# 6_Channels_TX_V1_Schematic.net
KiCad netlist of a schematic drawn in Altium Designer
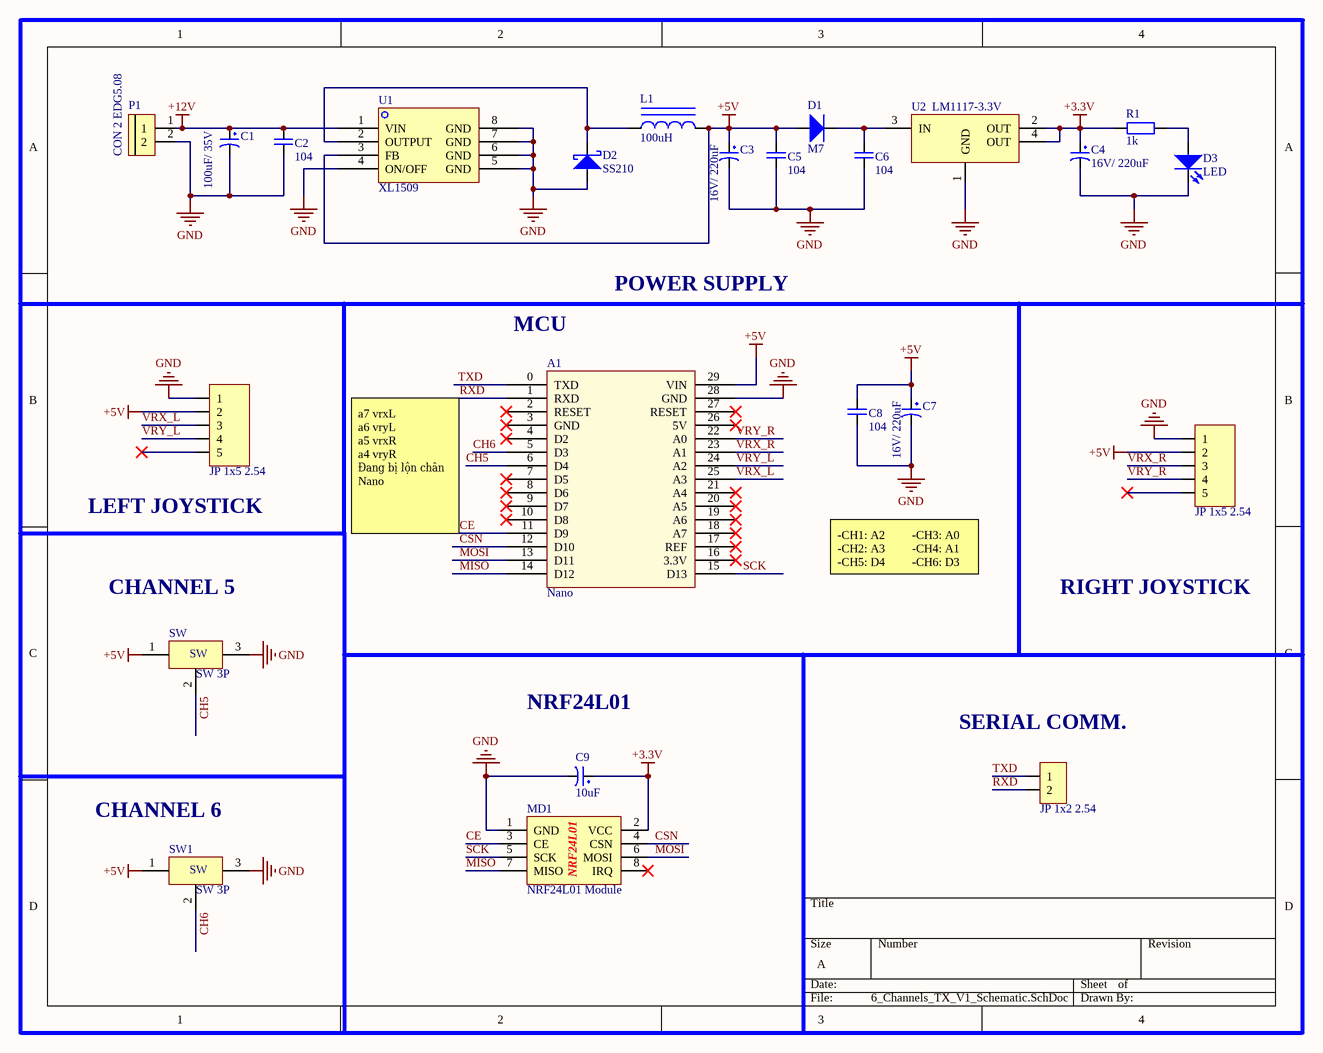
[diagram p0: 6_Channels_TX_V1_Schematic.SchDoc]

(export (version "E")
  (design (tool "Eeschema 10.0.6"))
  (components
    (comp (ref "A1")
      (value "Nano")
      (footprint "Arduino nano")
      (libsource (lib "Altium_Lib_by_KhueNguyenCreator") (part "Arduino Nano"))
    )
    (comp (ref "C1")
      (value "100uF/ 35V")
      (footprint "CAP SMD ALUMINUM D8")
      (libsource (lib "Electronic4u") (part "Cap_Polar"))
    )
    (comp (ref "C2")
      (value "104")
      (footprint "SM-0805")
      (libsource (lib "Electronic4u") (part "Cap_Non-Polar"))
    )
    (comp (ref "C3")
      (value "16V/ 220uF")
      (footprint "CAP SMD ALUMINUM D8")
      (libsource (lib "Electronic4u") (part "Cap_Polar"))
    )
    (comp (ref "C4")
      (value "16V/ 220uF")
      (footprint "CAP SMD ALUMINUM D8")
      (libsource (lib "Electronic4u") (part "Cap_Polar"))
    )
    (comp (ref "C5")
      (value "104")
      (footprint "SM-0805")
      (libsource (lib "Electronic4u") (part "Cap_Non-Polar"))
    )
    (comp (ref "C6")
      (value "104")
      (footprint "SM-0805")
      (libsource (lib "Electronic4u") (part "Cap_Non-Polar"))
    )
    (comp (ref "C7")
      (value "16V/ 220uF")
      (footprint "CAP SMD ALUMINUM D8")
      (libsource (lib "Electronic4u") (part "Cap_Polar"))
    )
    (comp (ref "C8")
      (value "104")
      (footprint "SM-0805")
      (libsource (lib "Electronic4u") (part "Cap_Non-Polar"))
    )
    (comp (ref "C9")
      (value "10uF")
      (footprint "tu hoa 8mm")
      (description "Cắm")
      (libsource (lib "Altium_Lib_by_KhueNguyenCreator") (part "Tu Hoa 100uF 35V 8x11"))
    )
    (comp (ref "D1")
      (value "M7")
      (footprint "DO-214AC")
      (description "Diode Standard")
      (fields (field (name "PART NUMBER") "LED 3 ly Single Colour"))
      (libsource (lib "Electronic4u") (part "Diode Standard"))
    )
    (comp (ref "D2")
      (value "SS210")
      (footprint "DO-214AC")
      (description "Diode Schottky")
      (fields (field (name "PART NUMBER") "LED 3 ly Single Colour"))
      (libsource (lib "Electronic4u") (part "Diode Schottky"))
    )
    (comp (ref "D3")
      (value "LED")
      (footprint "LED-3MM GRE")
      (description "LED Single")
      (libsource (lib "Electronic4u") (part "LED"))
    )
    (comp (ref "JP1")
      (value "JP 1x5 2.54")
      (footprint "JP 1x5 CC")
      (description "Cắm")
      (libsource (lib "Altium_Lib_by_KhueNguyenCreator") (part "JP 1x5 2.54 Cai Cong"))
    )
    (comp (ref "JP2")
      (value "JP 1x5 2.54")
      (footprint "JP 1x5 CC")
      (description "Cắm")
      (libsource (lib "Altium_Lib_by_KhueNguyenCreator") (part "JP 1x5 2.54 Cai Cong"))
    )
    (comp (ref "JP3")
      (value "JP 1x2 2.54")
      (footprint "JP 1x2 DT")
      (description "Cắm")
      (libsource (lib "Altium_Lib_by_KhueNguyenCreator") (part "JP 1x2 2.54 Duc Thang"))
    )
    (comp (ref "L1")
      (value "100uH")
      (footprint "INDUCTOR SMD 7342 7.3X7.3X4.2mm")
      (description "Magnetic-Core Inductor")
      (libsource (lib "Electronic4u") (part "Inductor Iron"))
    )
    (comp (ref "MD1")
      (value "NRF24L01 Module")
      (footprint "NRF24L01")
      (libsource (lib "Altium_Lib_by_KhueNguyenCreator") (part "NRF24L01 Module"))
    )
    (comp (ref "P1")
      (value "CON 2 EDG5.08")
      (footprint "CON 2 2EDG5.08")
      (description "Cắm")
      (libsource (lib "Altium_Lib_by_KhueNguyenCreator") (part "CON 2 EDG5.08"))
    )
    (comp (ref "R1")
      (value "1k")
      (footprint "RESISTOR SMD 0805")
      (libsource (lib "Electronic4u") (part "Resistor"))
    )
    (comp (ref "SW") (value "SW 3P") (footprint "MTS-102") (libsource (lib "FMS_PcbLib1") (part "SW 3P")))
    (comp (ref "SW1") (value "SW 3P") (footprint "MTS-102") (libsource (lib "FMS_PcbLib1") (part "SW 3P")))
    (comp (ref "U1")
      (value "XL1509")
      (footprint "SOP8")
      (description "IC power sop8")
      (libsource (lib "FMS_PcbLib1") (part "XL1509"))
    )
    (comp (ref "U2")
      (value "LM1117-3.3V")
      (footprint "SOT223-4N")
      (description "800mA Low-Dropout Linear Regulator")
      (fields (field (name "CREATOR") "Nguyen Ba Bien"))
      (libsource (lib "Electronic4u") (part "LM1117"))
    )
  )
  (nets
    (net (code "1") (name "+3.3V") (class "Default")
      (node (ref "C4") (pin "1") (pinfunction "1_1") (pintype "passive"))
      (node (ref "C9") (pin "1") (pinfunction "1_1") (pintype "passive"))
      (node (ref "MD1") (pin "2") (pinfunction "VCC_2") (pintype "passive"))
      (node (ref "R1") (pin "1") (pinfunction "1_1") (pintype "passive"))
      (node (ref "U2") (pin "2") (pinfunction "OUT_2") (pintype "passive"))
      (node (ref "U2") (pin "4") (pinfunction "OUT_4") (pintype "passive"))
    )
    (net (code "2") (name "+5V") (class "Default")
      (node (ref "A1") (pin "29") (pinfunction "VIN_29") (pintype "passive"))
      (node (ref "C3") (pin "1") (pinfunction "1_1") (pintype "passive"))
      (node (ref "C5") (pin "2") (pinfunction "2_2") (pintype "passive"))
      (node (ref "C7") (pin "1") (pinfunction "1_1") (pintype "passive"))
      (node (ref "C8") (pin "2") (pinfunction "2_2") (pintype "passive"))
      (node (ref "D1") (pin "1") (pinfunction "1_1") (pintype "passive"))
      (node (ref "JP1") (pin "2") (pinfunction "2_2") (pintype "passive"))
      (node (ref "JP2") (pin "2") (pinfunction "2_2") (pintype "passive"))
      (node (ref "L1") (pin "2") (pinfunction "2_2") (pintype "passive"))
      (node (ref "SW") (pin "1") (pinfunction "1_1") (pintype "passive"))
      (node (ref "SW1") (pin "1") (pinfunction "1_1") (pintype "passive"))
      (node (ref "U1") (pin "3") (pinfunction "FB_3") (pintype "passive"))
    )
    (net (code "3") (name "+12V") (class "Default")
      (node (ref "C1") (pin "1") (pinfunction "1_1") (pintype "passive"))
      (node (ref "C2") (pin "2") (pinfunction "2_2") (pintype "passive"))
      (node (ref "P1") (pin "1") (pinfunction "1_1") (pintype "passive"))
      (node (ref "U1") (pin "1") (pinfunction "VIN_1") (pintype "passive"))
    )
    (net (code "4") (name "/CE") (class "Default")
      (node (ref "A1") (pin "11") (pinfunction "D9_11") (pintype "passive"))
      (node (ref "MD1") (pin "3") (pinfunction "CE_3") (pintype "passive"))
    )
    (net (code "5") (name "/CH5") (class "Default")
      (node (ref "A1") (pin "6") (pinfunction "D4_6") (pintype "passive"))
      (node (ref "SW") (pin "2") (pinfunction "2_2") (pintype "passive"))
    )
    (net (code "6") (name "/CH6") (class "Default")
      (node (ref "A1") (pin "5") (pinfunction "D3_5") (pintype "passive"))
      (node (ref "SW1") (pin "2") (pinfunction "2_2") (pintype "passive"))
    )
    (net (code "7") (name "/CSN") (class "Default")
      (node (ref "A1") (pin "12") (pinfunction "D10_12") (pintype "passive"))
      (node (ref "MD1") (pin "4") (pinfunction "CSN_4") (pintype "passive"))
    )
    (net (code "8") (name "/MISO") (class "Default")
      (node (ref "A1") (pin "14") (pinfunction "D12_14") (pintype "passive"))
      (node (ref "MD1") (pin "7") (pinfunction "MISO_7") (pintype "passive"))
    )
    (net (code "9") (name "/MOSI") (class "Default")
      (node (ref "A1") (pin "13") (pinfunction "D11_13") (pintype "passive"))
      (node (ref "MD1") (pin "6") (pinfunction "MOSI_6") (pintype "passive"))
    )
    (net (code "10") (name "/RXD") (class "Default")
      (node (ref "A1") (pin "1") (pinfunction "RXD_1") (pintype "passive"))
      (node (ref "JP3") (pin "2") (pinfunction "2_2") (pintype "passive"))
    )
    (net (code "11") (name "/SCK") (class "Default")
      (node (ref "A1") (pin "15") (pinfunction "D13_15") (pintype "passive"))
      (node (ref "MD1") (pin "5") (pinfunction "SCK_5") (pintype "passive"))
    )
    (net (code "12") (name "/TXD") (class "Default")
      (node (ref "A1") (pin "0") (pinfunction "TXD_0") (pintype "passive"))
      (node (ref "JP3") (pin "1") (pinfunction "1_1") (pintype "passive"))
    )
    (net (code "13") (name "/VRX_L") (class "Default")
      (node (ref "A1") (pin "25") (pinfunction "A3_25") (pintype "passive"))
      (node (ref "JP1") (pin "3") (pinfunction "3_3") (pintype "passive"))
    )
    (net (code "14") (name "/VRX_R") (class "Default")
      (node (ref "A1") (pin "23") (pinfunction "A1_23") (pintype "passive"))
      (node (ref "JP2") (pin "3") (pinfunction "3_3") (pintype "passive"))
    )
    (net (code "15") (name "/VRY_L") (class "Default")
      (node (ref "A1") (pin "24") (pinfunction "A2_24") (pintype "passive"))
      (node (ref "JP1") (pin "4") (pinfunction "4_4") (pintype "passive"))
    )
    (net (code "16") (name "/VRY_R") (class "Default")
      (node (ref "A1") (pin "22") (pinfunction "A0_22") (pintype "passive"))
      (node (ref "JP2") (pin "4") (pinfunction "4_4") (pintype "passive"))
    )
    (net (code "17") (name "GND") (class "Default")
      (node (ref "A1") (pin "28") (pinfunction "GND_28") (pintype "passive"))
      (node (ref "C1") (pin "2") (pinfunction "2_2") (pintype "passive"))
      (node (ref "C2") (pin "1") (pinfunction "1_1") (pintype "passive"))
      (node (ref "C3") (pin "2") (pinfunction "2_2") (pintype "passive"))
      (node (ref "C4") (pin "2") (pinfunction "2_2") (pintype "passive"))
      (node (ref "C5") (pin "1") (pinfunction "1_1") (pintype "passive"))
      (node (ref "C6") (pin "1") (pinfunction "1_1") (pintype "passive"))
      (node (ref "C7") (pin "2") (pinfunction "2_2") (pintype "passive"))
      (node (ref "C8") (pin "1") (pinfunction "1_1") (pintype "passive"))
      (node (ref "C9") (pin "2") (pinfunction "2_2") (pintype "passive"))
      (node (ref "D2") (pin "1") (pinfunction "1_1") (pintype "passive"))
      (node (ref "D3") (pin "2") (pinfunction "2_2") (pintype "passive"))
      (node (ref "JP1") (pin "1") (pinfunction "1_1") (pintype "passive"))
      (node (ref "JP2") (pin "1") (pinfunction "1_1") (pintype "passive"))
      (node (ref "MD1") (pin "1") (pinfunction "GND_1") (pintype "passive"))
      (node (ref "P1") (pin "2") (pinfunction "2_2") (pintype "passive"))
      (node (ref "SW") (pin "3") (pinfunction "3_3") (pintype "passive"))
      (node (ref "SW1") (pin "3") (pinfunction "3_3") (pintype "passive"))
      (node (ref "U1") (pin "4") (pinfunction "ON/OFF_4") (pintype "passive"))
      (node (ref "U1") (pin "5") (pinfunction "GND_5") (pintype "passive"))
      (node (ref "U1") (pin "6") (pinfunction "GND_6") (pintype "passive"))
      (node (ref "U1") (pin "7") (pinfunction "GND_7") (pintype "passive"))
      (node (ref "U1") (pin "8") (pinfunction "GND_8") (pintype "passive"))
      (node (ref "U2") (pin "1") (pinfunction "GND_1") (pintype "passive"))
    )
    (net (code "18") (name "Net-(D3-Pad1)") (class "Default")
      (node (ref "D3") (pin "1") (pinfunction "1_1") (pintype "passive"))
      (node (ref "R1") (pin "2") (pinfunction "2_2") (pintype "passive"))
    )
    (net (code "19") (name "Net-(U1-OUTPUT)") (class "Default")
      (node (ref "D2") (pin "2") (pinfunction "2_2") (pintype "passive"))
      (node (ref "L1") (pin "1") (pinfunction "1_1") (pintype "passive"))
      (node (ref "U1") (pin "2") (pinfunction "OUTPUT_2") (pintype "passive"))
    )
    (net (code "20") (name "Net-(U2-IN)") (class "Default")
      (node (ref "C6") (pin "2") (pinfunction "2_2") (pintype "passive"))
      (node (ref "D1") (pin "2") (pinfunction "2_2") (pintype "passive"))
      (node (ref "U2") (pin "3") (pinfunction "IN_3") (pintype "passive"))
    )
    (net (code "21") (name "unconnected-(A1-3.3V-Pad16)") (class "Default")
      (node (ref "A1") (pin "16") (pinfunction "3.3V_16") (pintype "passive+no_connect"))
    )
    (net (code "22") (name "unconnected-(A1-5V-Pad26)") (class "Default")
      (node (ref "A1") (pin "26") (pinfunction "5V_26") (pintype "passive+no_connect"))
    )
    (net (code "23") (name "unconnected-(A1-A4-Pad21)") (class "Default")
      (node (ref "A1") (pin "21") (pinfunction "A4_21") (pintype "passive+no_connect"))
    )
    (net (code "24") (name "unconnected-(A1-A5-Pad20)") (class "Default")
      (node (ref "A1") (pin "20") (pinfunction "A5_20") (pintype "passive+no_connect"))
    )
    (net (code "25") (name "unconnected-(A1-A6-Pad19)") (class "Default")
      (node (ref "A1") (pin "19") (pinfunction "A6_19") (pintype "passive+no_connect"))
    )
    (net (code "26") (name "unconnected-(A1-A7-Pad18)") (class "Default")
      (node (ref "A1") (pin "18") (pinfunction "A7_18") (pintype "passive+no_connect"))
    )
    (net (code "27") (name "unconnected-(A1-D2-Pad4)") (class "Default")
      (node (ref "A1") (pin "4") (pinfunction "D2_4") (pintype "passive+no_connect"))
    )
    (net (code "28") (name "unconnected-(A1-D5-Pad7)") (class "Default")
      (node (ref "A1") (pin "7") (pinfunction "D5_7") (pintype "passive+no_connect"))
    )
    (net (code "29") (name "unconnected-(A1-D6-Pad8)") (class "Default")
      (node (ref "A1") (pin "8") (pinfunction "D6_8") (pintype "passive+no_connect"))
    )
    (net (code "30") (name "unconnected-(A1-D7-Pad9)") (class "Default")
      (node (ref "A1") (pin "9") (pinfunction "D7_9") (pintype "passive+no_connect"))
    )
    (net (code "31") (name "unconnected-(A1-D8-Pad10)") (class "Default")
      (node (ref "A1") (pin "10") (pinfunction "D8_10") (pintype "passive+no_connect"))
    )
    (net (code "32") (name "unconnected-(A1-GND-Pad3)") (class "Default")
      (node (ref "A1") (pin "3") (pinfunction "GND_3") (pintype "passive+no_connect"))
    )
    (net (code "33") (name "unconnected-(A1-REF-Pad17)") (class "Default")
      (node (ref "A1") (pin "17") (pinfunction "REF_17") (pintype "passive+no_connect"))
    )
    (net (code "34") (name "unconnected-(A1-RESET-Pad2)") (class "Default")
      (node (ref "A1") (pin "2") (pinfunction "RESET_2") (pintype "passive+no_connect"))
    )
    (net (code "35") (name "unconnected-(A1-RESET-Pad27)") (class "Default")
      (node (ref "A1") (pin "27") (pinfunction "RESET_27") (pintype "passive+no_connect"))
    )
    (net (code "36") (name "unconnected-(JP1-Pad5)") (class "Default")
      (node (ref "JP1") (pin "5") (pinfunction "5_5") (pintype "passive+no_connect"))
    )
    (net (code "37") (name "unconnected-(JP2-Pad5)") (class "Default")
      (node (ref "JP2") (pin "5") (pinfunction "5_5") (pintype "passive+no_connect"))
    )
    (net (code "38") (name "unconnected-(MD1-IRQ-Pad8)") (class "Default")
      (node (ref "MD1") (pin "8") (pinfunction "IRQ_8") (pintype "passive+no_connect"))
    )
  )
)
